# eth_100base-tx_magnetics.net
KiCad netlist of a schematic drawn in Altium Designer
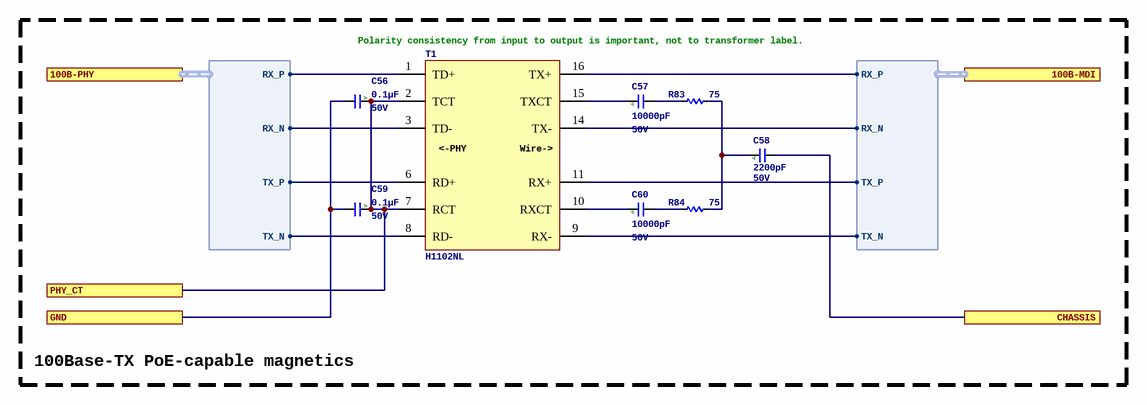
[diagram p0: eth_100base-tx_magnetics.SchDoc]

(export (version "E")
  (design (tool "Eeschema 10.0.6"))
  (components
    (comp (ref "C56")
      (value "CGA2B3X7R1H104M050BB")
      (footprint "C0402_0.55MM")
      (description "CAP CER 0.1UF 50V X7R 0402")
      (fields
        (field (name "CAPACITANCE") "0.1µF")
        (field (name "VOLTAGE - RATED") "50V")
        (field (name "TOLERANCE") "±20%")
        (field (name "MANUFACTURER") "TDK Corporation")
      )
      (libsource (lib "sscp") (part "__template_cap_auto"))
    )
    (comp (ref "C57")
      (value "CGJ2B3X7R1H103K050BB")
      (footprint "C0402_0.50MM")
      (description "CAP CER 10000PF 50V X7R 0402")
      (fields
        (field (name "CAPACITANCE") "10000pF")
        (field (name "VOLTAGE - RATED") "50V")
        (field (name "TOLERANCE") "±10%")
        (field (name "MANUFACTURER") "TDK Corporation")
      )
      (libsource (lib "sscp") (part "__template_cap_auto"))
    )
    (comp (ref "C58")
      (value "CGA2B2X7R1H222M050BA")
      (footprint "C0402_0.55MM")
      (description "CAP CER 2200PF 50V X7R 0402")
      (fields
        (field (name "CAPACITANCE") "2200pF")
        (field (name "VOLTAGE - RATED") "50V")
        (field (name "TOLERANCE") "±20%")
        (field (name "MANUFACTURER") "TDK Corporation")
      )
      (libsource (lib "sscp") (part "__template_cap_auto"))
    )
    (comp (ref "C59")
      (value "CGA2B3X7R1H104M050BB")
      (footprint "C0402_0.55MM")
      (description "CAP CER 0.1UF 50V X7R 0402")
      (fields
        (field (name "CAPACITANCE") "0.1µF")
        (field (name "VOLTAGE - RATED") "50V")
        (field (name "TOLERANCE") "±20%")
        (field (name "MANUFACTURER") "TDK Corporation")
      )
      (libsource (lib "sscp") (part "__template_cap_auto"))
    )
    (comp (ref "C60")
      (value "CGJ2B3X7R1H103K050BB")
      (footprint "C0402_0.50MM")
      (description "CAP CER 10000PF 50V X7R 0402")
      (fields
        (field (name "CAPACITANCE") "10000pF")
        (field (name "VOLTAGE - RATED") "50V")
        (field (name "TOLERANCE") "±10%")
        (field (name "MANUFACTURER") "TDK Corporation")
      )
      (libsource (lib "sscp") (part "__template_cap_auto"))
    )
    (comp (ref "R83")
      (value "ERJ-2RKF75R0X")
      (footprint "R0402_0.40MM")
      (description "RES SMD 75 OHM 1% 1/10W 0402")
      (fields
        (field (name "RESISTANCE") "75")
        (field (name "TOLERANCE") "±1%")
        (field (name "MANUFACTURER") "Panasonic Electronic Components")
      )
      (libsource (lib "sscp") (part "__template_resistor"))
    )
    (comp (ref "R84")
      (value "ERJ-2RKF75R0X")
      (footprint "R0402_0.40MM")
      (description "RES SMD 75 OHM 1% 1/10W 0402")
      (fields
        (field (name "RESISTANCE") "75")
        (field (name "TOLERANCE") "±1%")
        (field (name "MANUFACTURER") "Panasonic Electronic Components")
      )
      (libsource (lib "sscp") (part "__template_resistor"))
    )
    (comp (ref "T1")
      (value "H1102NL")
      (footprint "EPCOS_LAN_MODULE")
      (description "MODULE XFRMR SGL ETHR LAN 16SOIC")
      (fields
        (field (name "MANUFACTURER") "Pulse Electronics Corporation")
        (field (name "MANUFACTURER PART NUMBER") "H1102NL")
      )
      (libsource (lib "SSCP") (part "ETH_H1102NL"))
    )
  )
  (nets
    (net (code "2") (name "/CHASSIS") (class "Default") (node (ref "C58") (pin "2") (pintype "passive")))
    (net (code "3") (name "/GND") (class "Default")
      (node (ref "C56") (pin "2") (pintype "passive"))
      (node (ref "C59") (pin "2") (pintype "passive"))
    )
    (net (code "4") (name "/PHY_CT") (class "Default")
      (node (ref "C56") (pin "1") (pintype "passive"))
      (node (ref "C59") (pin "1") (pintype "passive"))
      (node (ref "T1") (pin "2") (pinfunction "TCT_2") (pintype "passive"))
      (node (ref "T1") (pin "7") (pinfunction "RCT_7") (pintype "passive"))
    )
    (net (code "6") (name "Net-(C57-Pad2)") (class "Default")
      (node (ref "C57") (pin "2") (pintype "passive"))
      (node (ref "R83") (pin "2") (pintype "passive"))
    )
    (net (code "7") (name "Net-(C58-Pad1)") (class "Default")
      (node (ref "C58") (pin "1") (pintype "passive"))
      (node (ref "R83") (pin "1") (pintype "passive"))
      (node (ref "R84") (pin "1") (pintype "passive"))
    )
    (net (code "8") (name "Net-(C60-Pad2)") (class "Default")
      (node (ref "C60") (pin "2") (pintype "passive"))
      (node (ref "R84") (pin "2") (pintype "passive"))
    )
    (net (code "9") (name "Net-(T1-RXCT)") (class "Default")
      (node (ref "C60") (pin "1") (pintype "passive"))
      (node (ref "T1") (pin "10") (pinfunction "RXCT_10") (pintype "passive"))
    )
    (net (code "10") (name "Net-(T1-TXCT)") (class "Default")
      (node (ref "C57") (pin "1") (pintype "passive"))
      (node (ref "T1") (pin "15") (pinfunction "TXCT_15") (pintype "passive"))
    )
    (net (code "11") (name "unconnected-(T1-RD+-Pad6)") (class "Default")
      (node (ref "T1") (pin "6") (pinfunction "RD+_6") (pintype "passive"))
    )
    (net (code "12") (name "unconnected-(T1-RD--Pad8)") (class "Default")
      (node (ref "T1") (pin "8") (pinfunction "RD-_8") (pintype "passive"))
    )
    (net (code "13") (name "unconnected-(T1-RX+-Pad11)") (class "Default")
      (node (ref "T1") (pin "11") (pinfunction "RX+_11") (pintype "passive"))
    )
    (net (code "14") (name "unconnected-(T1-RX--Pad9)") (class "Default")
      (node (ref "T1") (pin "9") (pinfunction "RX-_9") (pintype "passive"))
    )
    (net (code "15") (name "unconnected-(T1-TD+-Pad1)") (class "Default")
      (node (ref "T1") (pin "1") (pinfunction "TD+_1") (pintype "passive"))
    )
    (net (code "16") (name "unconnected-(T1-TD--Pad3)") (class "Default")
      (node (ref "T1") (pin "3") (pinfunction "TD-_3") (pintype "passive"))
    )
    (net (code "17") (name "unconnected-(T1-TX+-Pad16)") (class "Default")
      (node (ref "T1") (pin "16") (pinfunction "TX+_16") (pintype "passive"))
    )
    (net (code "18") (name "unconnected-(T1-TX--Pad14)") (class "Default")
      (node (ref "T1") (pin "14") (pinfunction "TX-_14") (pintype "passive"))
    )
  )
)
